# LiBatteryChargeBoostBoard.net
KiCad netlist of a schematic drawn in EAGLE
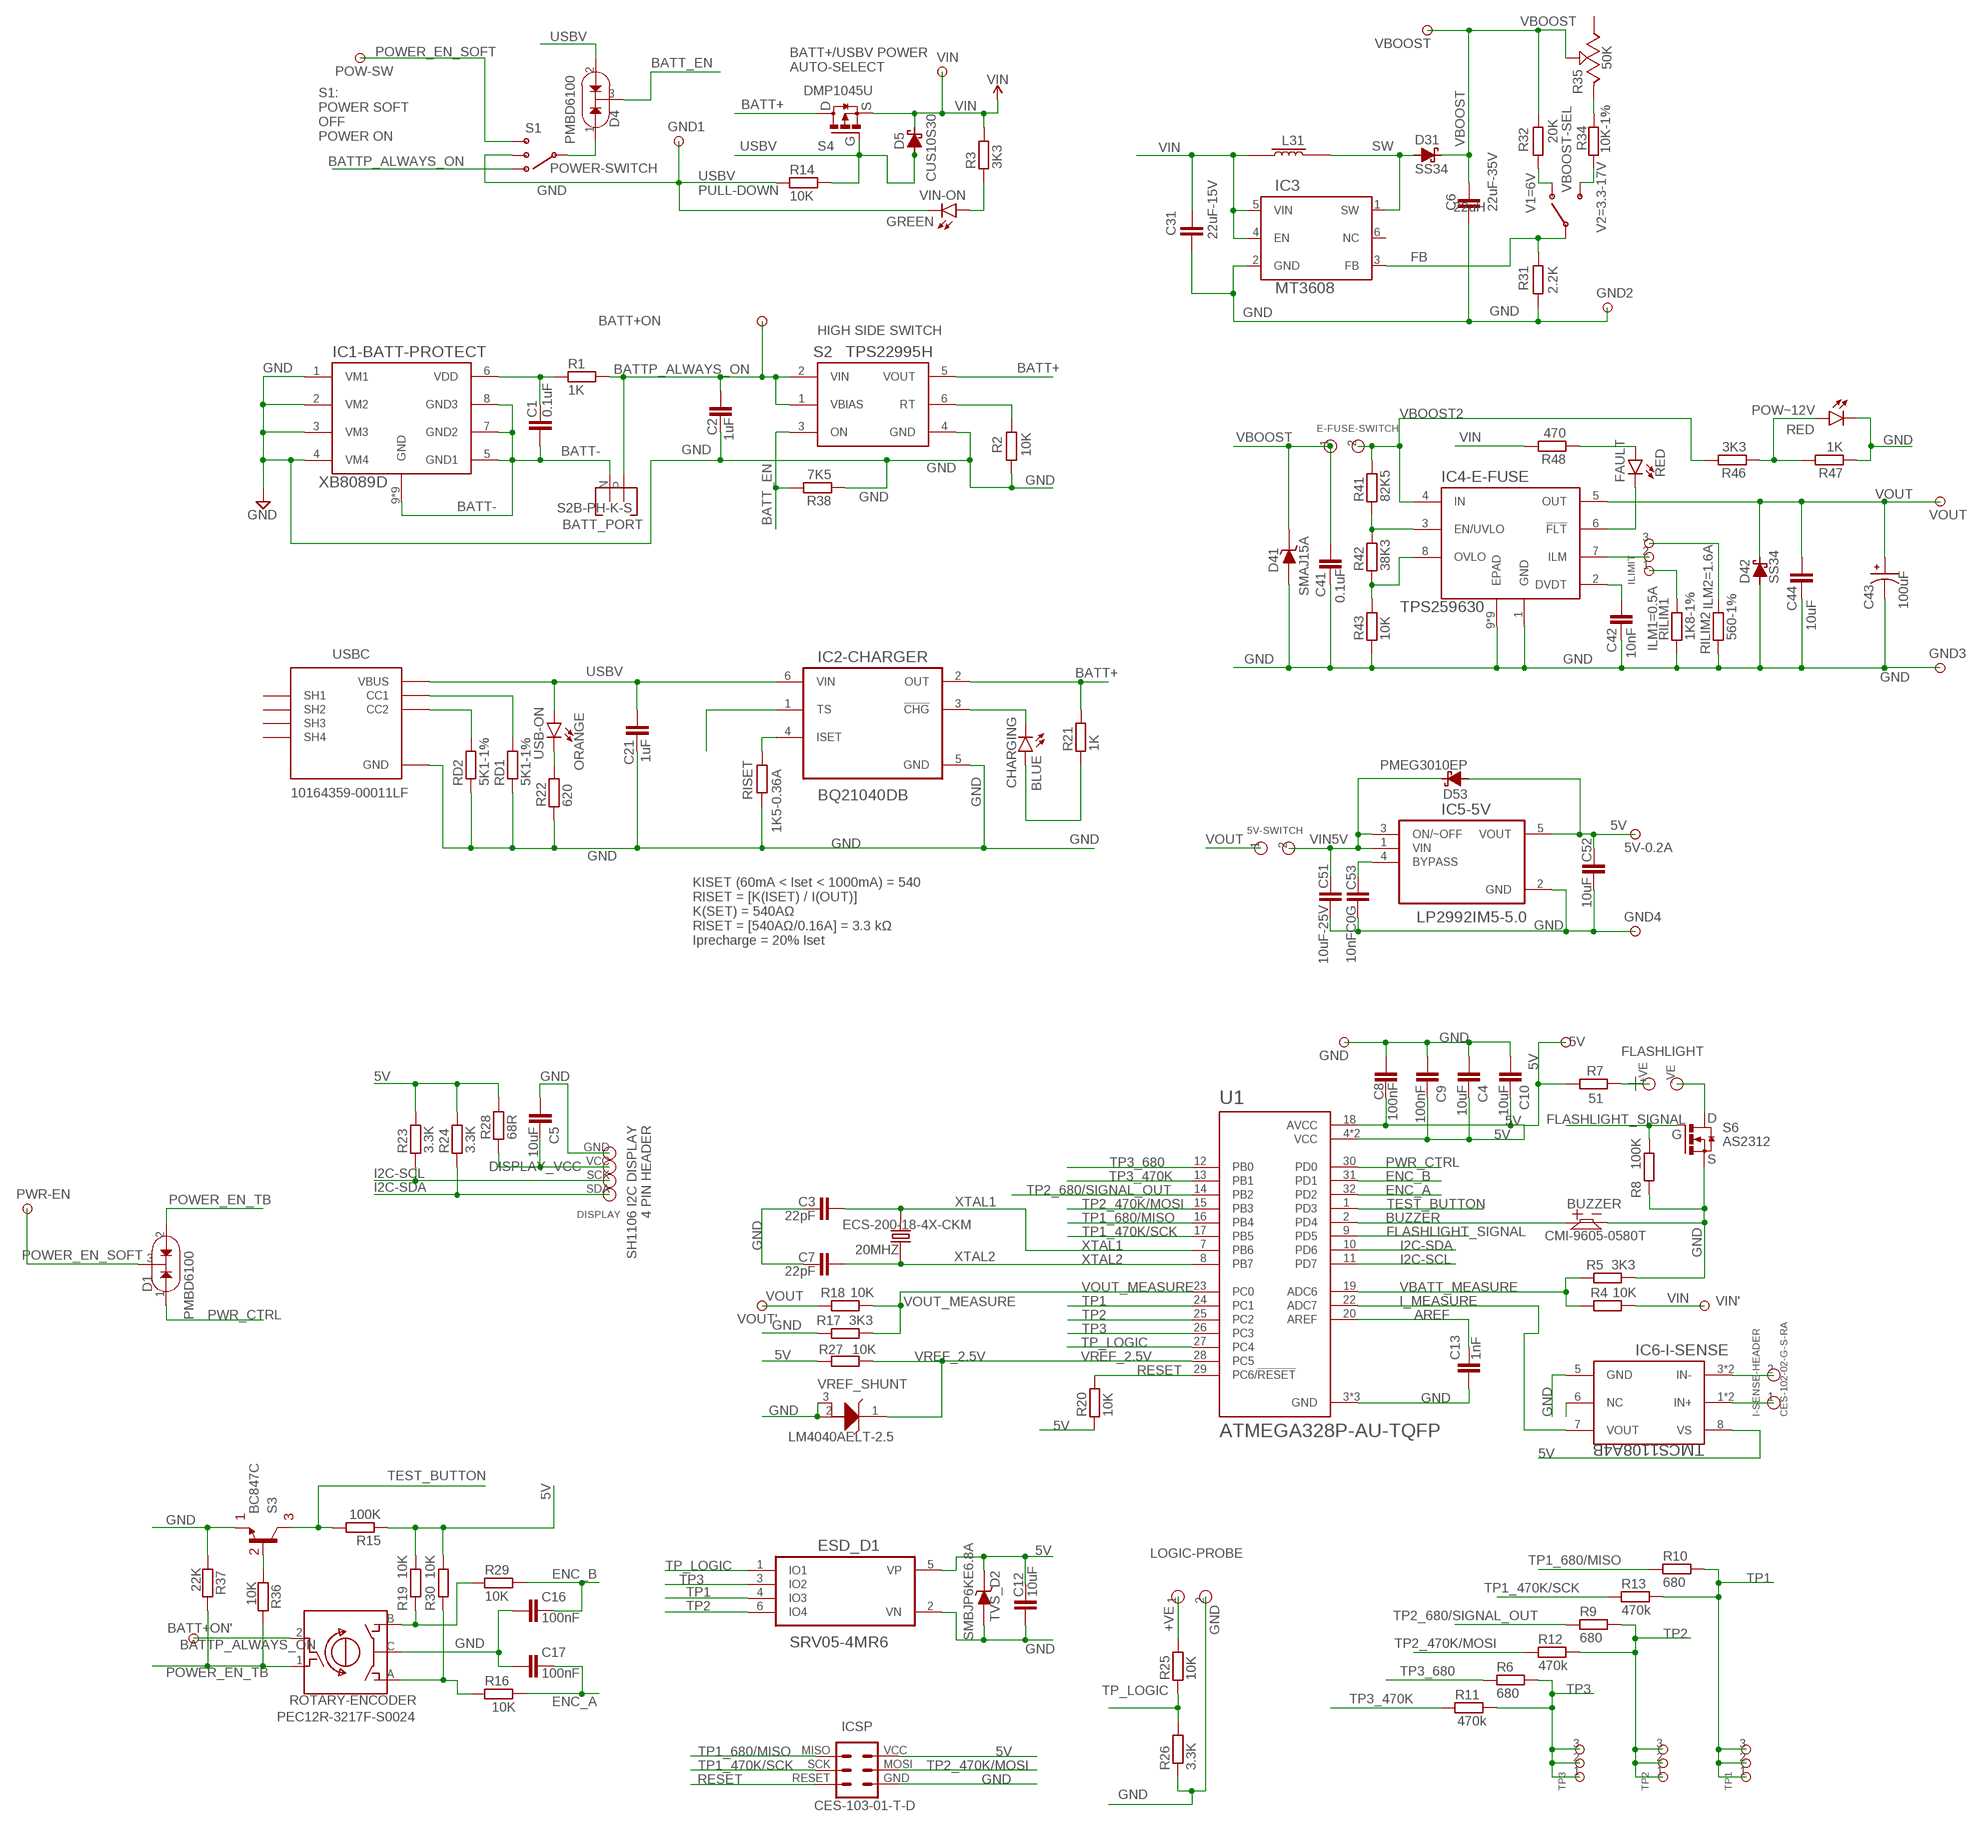
[diagram p0: schematic, sheet 1]

(export (version "E")
  (design (tool "Eeschema 10.0.6"))
  (components
    (comp (ref "5V")
      (value "TEST-POINT-TH")
      (footprint "eagle-import:TEST-POINT-TH-1MM")
      (libsource (lib "eagle-import") (part "TEST-POINT-TH"))
    )
    (comp (ref "5V-0.2A")
      (value "TEST-POINT-TH")
      (footprint "eagle-import:TEST-POINT-TH-1MM")
      (libsource (lib "eagle-import") (part "TEST-POINT-TH"))
    )
    (comp (ref "5V-SWITCH")
      (value "HEADER-2PIN-0.1\"P")
      (footprint "eagle-import:HEADER-2PIN-0.1_P")
      (libsource (lib "eagle-import") (part "HEADER-2PIN-0.1{dblquote}P"))
    )
    (comp (ref "20MHZ")
      (value "ECS-200-18-4X-CKM")
      (footprint "eagle-import:XTAL_ECS-200-18-4X-CKM")
      (fields (field (name "MF") "ECS Inc."))
      (libsource (lib "eagle-import") (part "CRYSTAL-20MHZ-ECS-200-18-4X-CKM"))
    )
    (comp (ref "BATT+ON")
      (value "TEST-POINT-TH")
      (footprint "eagle-import:TEST-POINT-TH-1MM")
      (libsource (lib "eagle-import") (part "TEST-POINT-TH"))
    )
    (comp (ref "BATT+ON'")
      (value "TEST-POINT-TH")
      (footprint "eagle-import:TEST-POINT-TH-1MM")
      (libsource (lib "eagle-import") (part "TEST-POINT-TH"))
    )
    (comp (ref "BATT_PORT")
      (value "S2B-PH-K-S")
      (footprint "eagle-import:S2B-PH-K-S")
      (libsource (lib "eagle-import") (part "S2B-PH-K-S"))
    )
    (comp (ref "BUZZER")
      (value "CMI-9605-0580T")
      (footprint "eagle-import:BUZZER-ACTIVE-CMI-9605-0580T")
      (libsource (lib "eagle-import") (part "BUZZER-ACTIVE-CMI-9605-0580T"))
    )
    (comp (ref "C1")
      (value "0.1uF")
      (footprint "eagle-import:0603")
      (libsource (lib "eagle-import") (part "CAPACITOR_SMD0603"))
    )
    (comp (ref "C2")
      (value "1uF")
      (footprint "eagle-import:0603")
      (libsource (lib "eagle-import") (part "CAPACITOR_SMD0603"))
    )
    (comp (ref "C3")
      (value "22pF")
      (footprint "eagle-import:0603")
      (libsource (lib "eagle-import") (part "CAPACITOR_SMD0603"))
    )
    (comp (ref "C4")
      (value "10uF")
      (footprint "eagle-import:0603")
      (libsource (lib "eagle-import") (part "CAPACITOR_SMD0603"))
    )
    (comp (ref "C5")
      (value "10uF")
      (footprint "eagle-import:0603")
      (libsource (lib "eagle-import") (part "CAPACITOR_SMD0603"))
    )
    (comp (ref "C6")
      (value "22uF-35V")
      (footprint "eagle-import:1206")
      (libsource (lib "eagle-import") (part "CAPACITOR_SMD1206"))
    )
    (comp (ref "C7")
      (value "22pF")
      (footprint "eagle-import:0603")
      (libsource (lib "eagle-import") (part "CAPACITOR_SMD0603"))
    )
    (comp (ref "C8")
      (value "100nF")
      (footprint "eagle-import:0603")
      (libsource (lib "eagle-import") (part "CAPACITOR_SMD0603"))
    )
    (comp (ref "C9")
      (value "100nF")
      (footprint "eagle-import:0603")
      (libsource (lib "eagle-import") (part "CAPACITOR_SMD0603"))
    )
    (comp (ref "C10")
      (value "10uF")
      (footprint "eagle-import:0603")
      (libsource (lib "eagle-import") (part "CAPACITOR_SMD0603"))
    )
    (comp (ref "C12")
      (value "10uF")
      (footprint "eagle-import:0603")
      (libsource (lib "eagle-import") (part "CAPACITOR_SMD0603"))
    )
    (comp (ref "C13")
      (value "1nF")
      (footprint "eagle-import:0603")
      (libsource (lib "eagle-import") (part "CAPACITOR_SMD0603"))
    )
    (comp (ref "C16")
      (value "100nF")
      (footprint "eagle-import:0603")
      (libsource (lib "eagle-import") (part "CAPACITOR_SMD0603"))
    )
    (comp (ref "C17")
      (value "100nF")
      (footprint "eagle-import:0603")
      (libsource (lib "eagle-import") (part "CAPACITOR_SMD0603"))
    )
    (comp (ref "C21")
      (value "1uF")
      (footprint "eagle-import:0603")
      (libsource (lib "eagle-import") (part "CAPACITOR_SMD0603"))
    )
    (comp (ref "C31")
      (value "22uF-15V")
      (footprint "eagle-import:1206")
      (libsource (lib "eagle-import") (part "CAPACITOR_SMD1206"))
    )
    (comp (ref "C41")
      (value "0.1uF")
      (footprint "eagle-import:0603")
      (libsource (lib "eagle-import") (part "CAPACITOR_SMD0603"))
    )
    (comp (ref "C42")
      (value "10nF")
      (footprint "eagle-import:0603")
      (libsource (lib "eagle-import") (part "CAPACITOR_SMD0603"))
    )
    (comp (ref "C43")
      (value "100uF")
      (footprint "eagle-import:CAP_EEEFN1E101UP")
      (fields (field (name "MF") "Panasonic Electronic Components") (field (name "MP") "EEE-FN1E101UP"))
      (libsource (lib "eagle-import") (part "EEEFN1E101UP"))
    )
    (comp (ref "C44")
      (value "10uF")
      (footprint "eagle-import:0603")
      (libsource (lib "eagle-import") (part "CAPACITOR_SMD0603"))
    )
    (comp (ref "C51")
      (value "10uF-25V")
      (footprint "eagle-import:0603")
      (libsource (lib "eagle-import") (part "CAPACITOR0603"))
    )
    (comp (ref "C52")
      (value "10uF")
      (footprint "eagle-import:0603")
      (libsource (lib "eagle-import") (part "CAPACITOR0603"))
    )
    (comp (ref "C53")
      (value "10nFC0G")
      (footprint "eagle-import:0603")
      (libsource (lib "eagle-import") (part "CAPACITOR_SMD0603"))
    )
    (comp (ref "CHARGING")
      (value "BLUE")
      (footprint "eagle-import:0603-DIODE")
      (libsource (lib "eagle-import") (part "LED0603"))
    )
    (comp (ref "D1")
      (value "PMBD6100")
      (footprint "eagle-import:SOT-23-3")
      (libsource (lib "eagle-import") (part "DIODE-DOUBLE-COMMON-CATHODE-PMBD6100,215"))
    )
    (comp (ref "D4")
      (value "PMBD6100")
      (footprint "eagle-import:SOT-23-3")
      (libsource (lib "eagle-import") (part "DIODE-DOUBLE-COMMON-CATHODE-PMBD6100,215"))
    )
    (comp (ref "D5")
      (value "CUS10S30")
      (footprint "eagle-import:SOD-323")
      (libsource (lib "eagle-import") (part "DIODE-SCHOTTKY-CUS10S30,H3F"))
    )
    (comp (ref "D31")
      (value "SS34")
      (footprint "eagle-import:SMA")
      (libsource (lib "eagle-import") (part "DIODE-SCHOTTKY-SS34"))
    )
    (comp (ref "D41")
      (value "SMAJ15A")
      (footprint "eagle-import:SMA")
      (libsource (lib "eagle-import") (part "DIODE-TVS-SMA"))
    )
    (comp (ref "D42")
      (value "SS34")
      (footprint "eagle-import:SMA")
      (libsource (lib "eagle-import") (part "DIODE-SCHOTTKY-SS34"))
    )
    (comp (ref "D53")
      (value "PMEG3010EP")
      (footprint "eagle-import:SOD-128")
      (libsource (lib "eagle-import") (part "DIODE-SCHOTTKY-PMEG3010EP,115"))
    )
    (comp (ref "DISPLAY")
      (value "DISPLAY-1.3\"-SH1106-I2C")
      (footprint "eagle-import:DISPLAY-1.3_-SH1106-I2C")
      (libsource (lib "eagle-import") (part "DISPLAY-1.3{dblquote}-SH1106-I2C"))
    )
    (comp (ref "E-FUSE-SWITCH")
      (value "HEADER-2PIN-0.1\"P")
      (footprint "eagle-import:HEADER-2PIN-0.1_P")
      (libsource (lib "eagle-import") (part "HEADER-2PIN-0.1{dblquote}P"))
    )
    (comp (ref "ESD_D1")
      (value "SRV05-4MR6")
      (footprint "eagle-import:SOT-23-6")
      (fields (field (name "MF") "ON Semiconductor") (field (name "MP") "SRV05-4MR6T1G"))
      (libsource (lib "eagle-import") (part "SRV05-4MR6T1G"))
    )
    (comp (ref "FAULT")
      (value "RED")
      (footprint "eagle-import:0603-DIODE")
      (libsource (lib "eagle-import") (part "LED0603"))
    )
    (comp (ref "FLASHLIGHT")
      (value "HEADER-2PIN-0.2\"P")
      (footprint "eagle-import:HEADER-2PIN-0.2_P")
      (libsource (lib "eagle-import") (part "HEADER-2PIN-0.2{dblquote}P"))
    )
    (comp (ref "GND")
      (value "TEST-POINT-TH")
      (footprint "eagle-import:TEST-POINT-TH-1MM")
      (libsource (lib "eagle-import") (part "TEST-POINT-TH"))
    )
    (comp (ref "GND1")
      (value "TEST-POINT-TH")
      (footprint "eagle-import:TEST-POINT-TH-1MM")
      (libsource (lib "eagle-import") (part "TEST-POINT-TH"))
    )
    (comp (ref "GND2")
      (value "TEST-POINT-TH")
      (footprint "eagle-import:TEST-POINT-TH-1MM")
      (libsource (lib "eagle-import") (part "TEST-POINT-TH"))
    )
    (comp (ref "GND3")
      (value "TEST-POINT-TH")
      (footprint "eagle-import:TEST-POINT-TH-1MM")
      (libsource (lib "eagle-import") (part "TEST-POINT-TH"))
    )
    (comp (ref "GND4")
      (value "TEST-POINT-TH")
      (footprint "eagle-import:TEST-POINT-TH-1MM")
      (libsource (lib "eagle-import") (part "TEST-POINT-TH"))
    )
    (comp (ref "I-SENSE-HEADER")
      (value "CES-102-02-G-S-RA")
      (footprint "eagle-import:HEADER-2PIN-0.1_P")
      (libsource (lib "eagle-import") (part "HEADER-2PIN-0.1{dblquote}P"))
    )
    (comp (ref "IC1-BATT-PROTECT")
      (value "XB8089D")
      (footprint "eagle-import:SOIC-8-POWER-PAD")
      (libsource (lib "eagle-import") (part "XB8089D"))
    )
    (comp (ref "IC2-CHARGER")
      (value "BQ21040DB")
      (footprint "eagle-import:SOT-23-6")
      (fields (field (name "MF") "Texas Instruments") (field (name "MP") "BQ21040DBVR"))
      (libsource (lib "eagle-import") (part "BQ21040DBVR"))
    )
    (comp (ref "IC3")
      (value "MT3608")
      (footprint "eagle-import:SOT-23-6")
      (libsource (lib "eagle-import") (part "MT3608"))
    )
    (comp (ref "IC4-E-FUSE")
      (value "TPS259630")
      (footprint "eagle-import:SOIC-8-POWER-PAD")
      (libsource (lib "eagle-import") (part "TPS259621DDAR"))
    )
    (comp (ref "IC5-5V")
      (value "LP2992IM5-5.0")
      (footprint "eagle-import:SOT-23-5")
      (fields (field (name "MF") "Texas Instruments") (field (name "MP") "LP2992IM5-5.0/NOPB"))
      (libsource (lib "eagle-import") (part "LP2992IM5-5.0"))
    )
    (comp (ref "IC6-I-SENSE")
      (value "TMCS1108A4B")
      (footprint "eagle-import:SOIC-8")
      (libsource (lib "eagle-import") (part "TMCS1108A4B-CURRENT-SENSE"))
    )
    (comp (ref "ICSP")
      (value "CES-103-01-T-D")
      (footprint "eagle-import:HEADER-ICSP-0.1_P")
      (libsource (lib "eagle-import") (part "HEADER-ICSP-0.1{dblquote}P"))
    )
    (comp (ref "ILIMIT")
      (value "HEADER-3PIN-0.1\"P")
      (footprint "eagle-import:HEADER-3PIN-0.1_P")
      (libsource (lib "eagle-import") (part "HEADER-3PIN-0.1{dblquote}P"))
    )
    (comp (ref "L31")
      (value "22uH")
      (footprint "eagle-import:INDUCTOR-SMRH74-220MT")
      (libsource (lib "eagle-import") (part "INDUCTOR-SMRH74-220MT"))
    )
    (comp (ref "LOGIC-PROBE")
      (value "HEADER-2PIN-0.1\"P")
      (footprint "eagle-import:HEADER-2PIN-0.1_P")
      (libsource (lib "eagle-import") (part "HEADER-2PIN-0.1{dblquote}P"))
    )
    (comp (ref "POW-SW")
      (value "TEST-POINT-TH")
      (footprint "eagle-import:TEST-POINT-TH-1MM")
      (libsource (lib "eagle-import") (part "TEST-POINT-TH"))
    )
    (comp (ref "POW~12V")
      (value "RED")
      (footprint "eagle-import:1206-DIODE")
      (libsource (lib "eagle-import") (part "LED1206"))
    )
    (comp (ref "PWR-EN")
      (value "TEST-POINT-TH")
      (footprint "eagle-import:TEST-POINT-TH-1MM")
      (libsource (lib "eagle-import") (part "TEST-POINT-TH"))
    )
    (comp (ref "R1")
      (value "1K")
      (footprint "eagle-import:0603")
      (libsource (lib "eagle-import") (part "RESISTOR_SMD0603"))
    )
    (comp (ref "R2")
      (value "10K")
      (footprint "eagle-import:0603")
      (libsource (lib "eagle-import") (part "RESISTOR_SMD0603"))
    )
    (comp (ref "R3")
      (value "3K3")
      (footprint "eagle-import:0603")
      (libsource (lib "eagle-import") (part "RESISTOR_SMD0603"))
    )
    (comp (ref "R4")
      (value "10K")
      (footprint "eagle-import:0603")
      (libsource (lib "eagle-import") (part "RESISTOR_SMD0603"))
    )
    (comp (ref "R5")
      (value "3K3")
      (footprint "eagle-import:0603")
      (libsource (lib "eagle-import") (part "RESISTOR_SMD0603"))
    )
    (comp (ref "R6")
      (value "680")
      (footprint "eagle-import:1206")
      (libsource (lib "eagle-import") (part "RESISTOR_SMD1206"))
    )
    (comp (ref "R7")
      (value "51")
      (footprint "eagle-import:1206")
      (libsource (lib "eagle-import") (part "RESISTOR_SMD1206"))
    )
    (comp (ref "R8")
      (value "100K")
      (footprint "eagle-import:0603")
      (libsource (lib "eagle-import") (part "RESISTOR_SMD0603"))
    )
    (comp (ref "R9")
      (value "680")
      (footprint "eagle-import:1206")
      (libsource (lib "eagle-import") (part "RESISTOR_SMD1206"))
    )
    (comp (ref "R10")
      (value "680")
      (footprint "eagle-import:1206")
      (libsource (lib "eagle-import") (part "RESISTOR_SMD1206"))
    )
    (comp (ref "R11")
      (value "470k")
      (footprint "eagle-import:1206")
      (libsource (lib "eagle-import") (part "RESISTOR_SMD1206"))
    )
    (comp (ref "R12")
      (value "470k")
      (footprint "eagle-import:1206")
      (libsource (lib "eagle-import") (part "RESISTOR_SMD1206"))
    )
    (comp (ref "R13")
      (value "470k")
      (footprint "eagle-import:1206")
      (libsource (lib "eagle-import") (part "RESISTOR_SMD1206"))
    )
    (comp (ref "R14")
      (value "10K")
      (footprint "eagle-import:0603")
      (libsource (lib "eagle-import") (part "RESISTOR_SMD0603"))
    )
    (comp (ref "R15")
      (value "100K")
      (footprint "eagle-import:0603")
      (libsource (lib "eagle-import") (part "RESISTOR_SMD0603"))
    )
    (comp (ref "R16")
      (value "10K")
      (footprint "eagle-import:0603")
      (libsource (lib "eagle-import") (part "RESISTOR_SMD0603"))
    )
    (comp (ref "R17")
      (value "3K3")
      (footprint "eagle-import:0603")
      (libsource (lib "eagle-import") (part "RESISTOR_SMD0603"))
    )
    (comp (ref "R18")
      (value "10K")
      (footprint "eagle-import:0603")
      (libsource (lib "eagle-import") (part "RESISTOR_SMD0603"))
    )
    (comp (ref "R19")
      (value "10K")
      (footprint "eagle-import:0603")
      (libsource (lib "eagle-import") (part "RESISTOR_SMD0603"))
    )
    (comp (ref "R20")
      (value "10K")
      (footprint "eagle-import:0603")
      (libsource (lib "eagle-import") (part "RESISTOR_SMD0603"))
    )
    (comp (ref "R21")
      (value "1K")
      (footprint "eagle-import:0603")
      (libsource (lib "eagle-import") (part "RESISTOR_SMD0603"))
    )
    (comp (ref "R22")
      (value "620")
      (footprint "eagle-import:0603")
      (libsource (lib "eagle-import") (part "RESISTOR_SMD0603"))
    )
    (comp (ref "R23")
      (value "3.3K")
      (footprint "eagle-import:0603")
      (libsource (lib "eagle-import") (part "RESISTOR_SMD0603"))
    )
    (comp (ref "R24")
      (value "3.3K")
      (footprint "eagle-import:0603")
      (libsource (lib "eagle-import") (part "RESISTOR_SMD0603"))
    )
    (comp (ref "R25")
      (value "10K")
      (footprint "eagle-import:0603")
      (libsource (lib "eagle-import") (part "RESISTOR_SMD0603"))
    )
    (comp (ref "R26")
      (value "3.3K")
      (footprint "eagle-import:0603")
      (libsource (lib "eagle-import") (part "RESISTOR_SMD0603"))
    )
    (comp (ref "R27")
      (value "10K")
      (footprint "eagle-import:0603")
      (libsource (lib "eagle-import") (part "RESISTOR_SMD0603"))
    )
    (comp (ref "R28")
      (value "68R")
      (footprint "eagle-import:0603")
      (libsource (lib "eagle-import") (part "RESISTOR_SMD0603"))
    )
    (comp (ref "R29")
      (value "10K")
      (footprint "eagle-import:0603")
      (libsource (lib "eagle-import") (part "RESISTOR_SMD0603"))
    )
    (comp (ref "R30")
      (value "10K")
      (footprint "eagle-import:0603")
      (libsource (lib "eagle-import") (part "RESISTOR_SMD0603"))
    )
    (comp (ref "R31")
      (value "2.2K")
      (footprint "eagle-import:0603")
      (libsource (lib "eagle-import") (part "RESISTOR_SMD0603"))
    )
    (comp (ref "R32")
      (value "20K")
      (footprint "eagle-import:0603")
      (libsource (lib "eagle-import") (part "RESISTOR_SMD0603"))
    )
    (comp (ref "R34")
      (value "10K-1%")
      (footprint "eagle-import:0603")
      (libsource (lib "eagle-import") (part "RESISTOR_SMD0603"))
    )
    (comp (ref "R35")
      (value "50K")
      (footprint "eagle-import:ROTARY-POTENTIOMETER-3386P")
      (libsource (lib "eagle-import") (part "ROTARY-POTENTIOMETER-3386P-1-503TLF"))
    )
    (comp (ref "R36")
      (value "10K")
      (footprint "eagle-import:0603")
      (libsource (lib "eagle-import") (part "RESISTOR_SMD0603"))
    )
    (comp (ref "R37")
      (value "22K")
      (footprint "eagle-import:0603")
      (libsource (lib "eagle-import") (part "RESISTOR_SMD0603"))
    )
    (comp (ref "R38")
      (value "7K5")
      (footprint "eagle-import:0603")
      (libsource (lib "eagle-import") (part "RESISTOR_SMD0603"))
    )
    (comp (ref "R41")
      (value "82K5")
      (footprint "eagle-import:0603")
      (libsource (lib "eagle-import") (part "RESISTOR_SMD0603"))
    )
    (comp (ref "R42")
      (value "38K3")
      (footprint "eagle-import:0603")
      (libsource (lib "eagle-import") (part "RESISTOR_SMD0603"))
    )
    (comp (ref "R43")
      (value "10K")
      (footprint "eagle-import:0603")
      (libsource (lib "eagle-import") (part "RESISTOR_SMD0603"))
    )
    (comp (ref "R46")
      (value "3K3")
      (footprint "eagle-import:0603")
      (libsource (lib "eagle-import") (part "RESISTOR_SMD0603"))
    )
    (comp (ref "R47")
      (value "1K")
      (footprint "eagle-import:0603")
      (libsource (lib "eagle-import") (part "RESISTOR_SMD0603"))
    )
    (comp (ref "R48")
      (value "470")
      (footprint "eagle-import:0603")
      (libsource (lib "eagle-import") (part "RESISTOR_SMD0603"))
    )
    (comp (ref "RD1")
      (value "5K1-1%")
      (footprint "eagle-import:0603")
      (libsource (lib "eagle-import") (part "RESISTOR_SMD0603"))
    )
    (comp (ref "RD2")
      (value "5K1-1%")
      (footprint "eagle-import:0603")
      (libsource (lib "eagle-import") (part "RESISTOR_SMD0603"))
    )
    (comp (ref "RILIM1")
      (value "1K8-1%")
      (footprint "eagle-import:0603")
      (libsource (lib "eagle-import") (part "RESISTOR_SMD0603"))
    )
    (comp (ref "RILIM2")
      (value "560-1%")
      (footprint "eagle-import:0603")
      (libsource (lib "eagle-import") (part "RESISTOR_SMD0603"))
    )
    (comp (ref "RISET")
      (value "1K5-0.36A")
      (footprint "eagle-import:0603")
      (libsource (lib "eagle-import") (part "RESISTOR_SMD0603"))
    )
    (comp (ref "ROTARY-ENCODER")
      (value "PEC12R-3217F-S0024")
      (footprint "eagle-import:PEC12R-3217F-S0024")
      (libsource (lib "eagle-import") (part "PEC12R-3217F-S0024"))
    )
    (comp (ref "S1")
      (value "POWER-SWITCH")
      (footprint "eagle-import:CSS-1310MC")
      (libsource (lib "eagle-import") (part "SLIDE-SWITCH-SP3T-VER-TH-MINI"))
    )
    (comp (ref "S2")
      (value "TPS22995H")
      (footprint "eagle-import:SOT-23-6")
      (libsource (lib "eagle-import") (part "TPS22995H-Q1"))
    )
    (comp (ref "S3")
      (value "BC847C")
      (footprint "eagle-import:SOT-23-3")
      (libsource (lib "eagle-import") (part "BC847C"))
    )
    (comp (ref "S4")
      (value "DMP1045U")
      (footprint "eagle-import:SOT-23-3")
      (libsource (lib "eagle-import") (part "DMP1045U"))
    )
    (comp (ref "S6")
      (value "AS2312")
      (footprint "eagle-import:SOT-23-3")
      (libsource (lib "eagle-import") (part "AS2312AS2312"))
    )
    (comp (ref "TP1")
      (value "HEADER-3PIN-0.1\"P")
      (footprint "eagle-import:HEADER-3PIN-0.1_P")
      (libsource (lib "eagle-import") (part "HEADER-3PIN-0.1{dblquote}P"))
    )
    (comp (ref "TP2")
      (value "HEADER-3PIN-0.1\"P")
      (footprint "eagle-import:HEADER-3PIN-0.1_P")
      (libsource (lib "eagle-import") (part "HEADER-3PIN-0.1{dblquote}P"))
    )
    (comp (ref "TP3")
      (value "HEADER-3PIN-0.1\"P")
      (footprint "eagle-import:HEADER-3PIN-0.1_P")
      (libsource (lib "eagle-import") (part "HEADER-3PIN-0.1{dblquote}P"))
    )
    (comp (ref "TVS_D2")
      (value "SMBJP6KE6.8A")
      (footprint "eagle-import:DIOM5336X244N")
      (fields
        (field (name "DIGIKEY_PART_NUMBER") "SMBJP6KE6.8A-TPMSTR-ND")
        (field (name "MF") "Micro Commercial")
        (field (name "MP") "SMBJP6KE6.8A-TP")
      )
      (libsource (lib "eagle-import") (part "SMBJP6KE6.8A-TP"))
    )
    (comp (ref "U1")
      (value "ATMEGA328P-AU-TQFP")
      (footprint "eagle-import:TQFP32")
      (fields (field (name "MF") "Microchip") (field (name "MP") "ATMEGA328P-AU"))
      (libsource (lib "eagle-import") (part "ATMEGA328P-AU-TQFP"))
    )
    (comp (ref "USB-ON")
      (value "ORANGE")
      (footprint "eagle-import:0603-DIODE")
      (libsource (lib "eagle-import") (part "LED0603"))
    )
    (comp (ref "USBC")
      (value "10164359-00011LF")
      (footprint "eagle-import:USB-C-RECEPTABLE-1016435900011LF")
      (fields (field (name "MF") "Amphenol FCI"))
      (libsource (lib "eagle-import") (part "USB-C-RECEPTABLE-10164359-00011LF"))
    )
    (comp (ref "VBOOST")
      (value "TEST-POINT-TH")
      (footprint "eagle-import:TEST-POINT-TH-1MM")
      (libsource (lib "eagle-import") (part "TEST-POINT-TH"))
    )
    (comp (ref "VBOOST-SEL")
      (value "SLIDE-SWITCH-SPDT-VERTICLE-TH")
      (footprint "eagle-import:SLW-883935-2A-D")
      (libsource (lib "eagle-import") (part "SLIDE-SWITCH-SPDT-VERTICLE-TH"))
    )
    (comp (ref "VIN")
      (value "TEST-POINT-TH")
      (footprint "eagle-import:TEST-POINT-TH-1MM")
      (libsource (lib "eagle-import") (part "TEST-POINT-TH"))
    )
    (comp (ref "VIN'")
      (value "TEST-POINT-TH")
      (footprint "eagle-import:TEST-POINT-TH-1MM")
      (libsource (lib "eagle-import") (part "TEST-POINT-TH"))
    )
    (comp (ref "VIN-ON")
      (value "GREEN")
      (footprint "eagle-import:0603-DIODE")
      (libsource (lib "eagle-import") (part "LED0603"))
    )
    (comp (ref "VOUT")
      (value "TEST-POINT-TH")
      (footprint "eagle-import:TEST-POINT-TH-1MM")
      (libsource (lib "eagle-import") (part "TEST-POINT-TH"))
    )
    (comp (ref "VOUT'")
      (value "TEST-POINT-TH")
      (footprint "eagle-import:TEST-POINT-TH-1MM")
      (libsource (lib "eagle-import") (part "TEST-POINT-TH"))
    )
    (comp (ref "VREF_SHUNT")
      (value "LM4040AELT-2.5")
      (footprint "eagle-import:SOT-23-3")
      (libsource (lib "eagle-import") (part "LM4040AELT-2.5-SOT23"))
    )
  )
  (nets
    (net (code "1") (name "/+VE") (class "Default")
      (node (ref "LOGIC-PROBE") (pin "1") (pinfunction "P$1_1") (pintype "bidirectional"))
      (node (ref "R25") (pin "2") (pinfunction "2_2") (pintype "passive"))
    )
    (net (code "2") (name "/5V") (class "Default")
      (node (ref "5V") (pin "P$1") (pinfunction "P$1_P$1") (pintype "bidirectional"))
      (node (ref "5V-0.2A") (pin "P$1") (pinfunction "P$1_P$1") (pintype "bidirectional"))
      (node (ref "C10") (pin "1") (pinfunction "1_1") (pintype "passive"))
      (node (ref "C12") (pin "1") (pinfunction "1_1") (pintype "passive"))
      (node (ref "C4") (pin "1") (pinfunction "1_1") (pintype "passive"))
      (node (ref "C52") (pin "2") (pinfunction "2_2") (pintype "passive"))
      (node (ref "C8") (pin "2") (pinfunction "2_2") (pintype "passive"))
      (node (ref "C9") (pin "1") (pinfunction "1_1") (pintype "passive"))
      (node (ref "D53") (pin "A") (pinfunction "A_A") (pintype "passive"))
      (node (ref "ESD_D1") (pin "5") (pinfunction "VP_5") (pintype "power_in"))
      (node (ref "IC5-5V") (pin "5") (pinfunction "VOUT_5") (pintype "output"))
      (node (ref "IC6-I-SENSE") (pin "8") (pinfunction "VS_8") (pintype "input"))
      (node (ref "ICSP") (pin "VCC") (pinfunction "2_VCC") (pintype "passive"))
      (node (ref "R15") (pin "1") (pinfunction "1_1") (pintype "passive"))
      (node (ref "R19") (pin "2") (pinfunction "2_2") (pintype "passive"))
      (node (ref "R20") (pin "1") (pinfunction "1_1") (pintype "passive"))
      (node (ref "R23") (pin "2") (pinfunction "2_2") (pintype "passive"))
      (node (ref "R24") (pin "2") (pinfunction "2_2") (pintype "passive"))
      (node (ref "R27") (pin "1") (pinfunction "1_1") (pintype "passive"))
      (node (ref "R28") (pin "2") (pinfunction "2_2") (pintype "passive"))
      (node (ref "R30") (pin "2") (pinfunction "2_2") (pintype "passive"))
      (node (ref "R7") (pin "1") (pinfunction "1_1") (pintype "passive"))
      (node (ref "TVS_D2") (pin "C") (pinfunction "C_C") (pintype "passive"))
      (node (ref "U1") (pin "18") (pinfunction "AVCC_18") (pintype "power_in"))
      (node (ref "U1") (pin "4") (pinfunction "VCC_4") (pintype "power_in"))
      (node (ref "U1") (pin "6") (pinfunction "VCC_6") (pintype "power_in"))
    )
    (net (code "3") (name "/AREF") (class "Default")
      (node (ref "C13") (pin "1") (pinfunction "1_1") (pintype "passive"))
      (node (ref "U1") (pin "20") (pinfunction "AREF_20") (pintype "input"))
    )
    (net (code "4") (name "/BATT+") (class "Default")
      (node (ref "IC2-CHARGER") (pin "2") (pinfunction "OUT_2") (pintype "output"))
      (node (ref "R21") (pin "2") (pinfunction "2_2") (pintype "passive"))
      (node (ref "S2") (pin "5") (pinfunction "VOUT_5") (pintype "output"))
      (node (ref "S4") (pin "3") (pinfunction "D_3") (pintype "passive"))
    )
    (net (code "5") (name "/BATT-") (class "Default")
      (node (ref "BATT_PORT") (pin "N") (pinfunction "N_N") (pintype "bidirectional"))
      (node (ref "C1") (pin "2") (pinfunction "2_2") (pintype "passive"))
      (node (ref "IC1-BATT-PROTECT") (pin "10") (pinfunction "GND_10") (pintype "power_in"))
      (node (ref "IC1-BATT-PROTECT") (pin "11") (pinfunction "GND_11") (pintype "power_in"))
      (node (ref "IC1-BATT-PROTECT") (pin "12") (pinfunction "GND_12") (pintype "power_in"))
      (node (ref "IC1-BATT-PROTECT") (pin "13") (pinfunction "GND_13") (pintype "power_in"))
      (node (ref "IC1-BATT-PROTECT") (pin "14") (pinfunction "GND_14") (pintype "power_in"))
      (node (ref "IC1-BATT-PROTECT") (pin "15") (pinfunction "GND_15") (pintype "power_in"))
      (node (ref "IC1-BATT-PROTECT") (pin "16") (pinfunction "GND_16") (pintype "power_in"))
      (node (ref "IC1-BATT-PROTECT") (pin "17") (pinfunction "GND_17") (pintype "power_in"))
      (node (ref "IC1-BATT-PROTECT") (pin "5") (pinfunction "GND1_5") (pintype "power_in"))
      (node (ref "IC1-BATT-PROTECT") (pin "7") (pinfunction "GND2_7") (pintype "power_in"))
      (node (ref "IC1-BATT-PROTECT") (pin "8") (pinfunction "GND3_8") (pintype "power_in"))
      (node (ref "IC1-BATT-PROTECT") (pin "9") (pinfunction "GND_9") (pintype "power_in"))
    )
    (net (code "6") (name "/BATTP_ALWAYS_ON") (class "Default")
      (node (ref "BATT+ON") (pin "P$1") (pinfunction "P$1_P$1") (pintype "bidirectional"))
      (node (ref "BATT+ON'") (pin "P$1") (pinfunction "P$1_P$1") (pintype "bidirectional"))
      (node (ref "BATT_PORT") (pin "P") (pinfunction "P_P") (pintype "bidirectional"))
      (node (ref "C2") (pin "2") (pinfunction "2_2") (pintype "passive"))
      (node (ref "R1") (pin "2") (pinfunction "2_2") (pintype "passive"))
      (node (ref "ROTARY-ENCODER") (pin "2") (pinfunction "2_2") (pintype "bidirectional"))
      (node (ref "S1") (pin "1") (pinfunction "1_1") (pintype "bidirectional"))
      (node (ref "S2") (pin "1") (pinfunction "VBIAS_1") (pintype "output"))
      (node (ref "S2") (pin "2") (pinfunction "VIN_2") (pintype "input"))
    )
    (net (code "7") (name "/BATT_EN") (class "Default")
      (node (ref "D4") (pin "3") (pinfunction "C_3") (pintype "bidirectional"))
      (node (ref "R38") (pin "2") (pinfunction "2_2") (pintype "passive"))
      (node (ref "S2") (pin "3") (pinfunction "ON_3") (pintype "input"))
    )
    (net (code "8") (name "/BUZZER") (class "Default")
      (node (ref "BUZZER") (pin "P$1") (pinfunction "P$1_P$1") (pintype "bidirectional"))
      (node (ref "U1") (pin "2") (pinfunction "PD4_2") (pintype "bidirectional"))
    )
    (net (code "9") (name "/DISPLAY_VCC") (class "Default")
      (node (ref "C5") (pin "1") (pinfunction "1_1") (pintype "passive"))
      (node (ref "DISPLAY") (pin "VCC") (pinfunction "VCC_VCC") (pintype "bidirectional"))
      (node (ref "R28") (pin "1") (pinfunction "1_1") (pintype "passive"))
    )
    (net (code "10") (name "/ENC_A") (class "Default")
      (node (ref "C17") (pin "1") (pinfunction "1_1") (pintype "passive"))
      (node (ref "R16") (pin "2") (pinfunction "2_2") (pintype "passive"))
      (node (ref "U1") (pin "32") (pinfunction "PD2_32") (pintype "bidirectional"))
    )
    (net (code "11") (name "/ENC_B") (class "Default")
      (node (ref "C16") (pin "1") (pinfunction "1_1") (pintype "passive"))
      (node (ref "R29") (pin "2") (pinfunction "2_2") (pintype "passive"))
      (node (ref "U1") (pin "31") (pinfunction "PD1_31") (pintype "bidirectional"))
    )
    (net (code "12") (name "/FB") (class "Default")
      (node (ref "IC3") (pin "3") (pinfunction "FB_3") (pintype "power_in"))
      (node (ref "R31") (pin "1") (pinfunction "1_1") (pintype "passive"))
      (node (ref "VBOOST-SEL") (pin "C") (pinfunction "C_C") (pintype "bidirectional"))
    )
    (net (code "13") (name "/FLASHLIGHT_SIGNAL") (class "Default")
      (node (ref "R8") (pin "1") (pinfunction "1_1") (pintype "passive"))
      (node (ref "S6") (pin "1") (pinfunction "G_1") (pintype "passive"))
      (node (ref "U1") (pin "9") (pinfunction "PD5_9") (pintype "bidirectional"))
    )
    (net (code "14") (name "/I2C-SCL") (class "Default")
      (node (ref "DISPLAY") (pin "SCK") (pinfunction "SCK_SCK") (pintype "bidirectional"))
      (node (ref "R23") (pin "1") (pinfunction "1_1") (pintype "passive"))
      (node (ref "U1") (pin "11") (pinfunction "PD7_11") (pintype "bidirectional"))
    )
    (net (code "15") (name "/I2C-SDA") (class "Default")
      (node (ref "DISPLAY") (pin "SDA") (pinfunction "SDA_SDA") (pintype "bidirectional"))
      (node (ref "R24") (pin "1") (pinfunction "1_1") (pintype "passive"))
      (node (ref "U1") (pin "10") (pinfunction "PD6_10") (pintype "bidirectional"))
    )
    (net (code "16") (name "/I_MEASURE") (class "Default")
      (node (ref "IC6-I-SENSE") (pin "7") (pinfunction "VOUT_7") (pintype "output"))
      (node (ref "U1") (pin "22") (pinfunction "ADC7_22") (pintype "bidirectional"))
    )
    (net (code "17") (name "/POWER_EN_SOFT") (class "Default")
      (node (ref "D1") (pin "3") (pinfunction "C_3") (pintype "bidirectional"))
      (node (ref "POW-SW") (pin "P$1") (pinfunction "P$1_P$1") (pintype "bidirectional"))
      (node (ref "PWR-EN") (pin "P$1") (pinfunction "P$1_P$1") (pintype "bidirectional"))
      (node (ref "S1") (pin "3") (pinfunction "3_3") (pintype "bidirectional"))
    )
    (net (code "18") (name "/POWER_EN_TB") (class "Default")
      (node (ref "D1") (pin "2") (pinfunction "A2_2") (pintype "bidirectional"))
      (node (ref "R36") (pin "2") (pinfunction "2_2") (pintype "passive"))
      (node (ref "R37") (pin "2") (pinfunction "2_2") (pintype "passive"))
      (node (ref "ROTARY-ENCODER") (pin "1") (pinfunction "1_1") (pintype "bidirectional"))
    )
    (net (code "19") (name "/PWR_CTRL") (class "Default")
      (node (ref "D1") (pin "1") (pinfunction "A1_1") (pintype "bidirectional"))
      (node (ref "U1") (pin "30") (pinfunction "PD0_30") (pintype "bidirectional"))
    )
    (net (code "20") (name "/RESET") (class "Default")
      (node (ref "ICSP") (pin "RESET") (pinfunction "5_RESET") (pintype "passive"))
      (node (ref "R20") (pin "2") (pinfunction "2_2") (pintype "passive"))
      (node (ref "U1") (pin "29") (pinfunction "PC6/~{RESET}_29") (pintype "bidirectional"))
    )
    (net (code "21") (name "/SW") (class "Default")
      (node (ref "D31") (pin "A") (pinfunction "A_A") (pintype "passive"))
      (node (ref "IC3") (pin "1") (pinfunction "SW_1") (pintype "output"))
      (node (ref "L31") (pin "P$2") (pinfunction "P$2_P$2") (pintype "bidirectional"))
    )
    (net (code "22") (name "/TEST_BUTTON") (class "Default")
      (node (ref "R15") (pin "2") (pinfunction "2_2") (pintype "passive"))
      (node (ref "S3") (pin "3") (pinfunction "C_3") (pintype "passive"))
      (node (ref "U1") (pin "1") (pinfunction "PD3_1") (pintype "bidirectional"))
    )
    (net (code "23") (name "/TP1") (class "Default")
      (node (ref "ESD_D1") (pin "4") (pinfunction "IO3_4") (pintype "input"))
      (node (ref "R10") (pin "2") (pinfunction "2_2") (pintype "passive"))
      (node (ref "R13") (pin "2") (pinfunction "2_2") (pintype "passive"))
      (node (ref "TP1") (pin "1") (pinfunction "P$1_1") (pintype "bidirectional"))
      (node (ref "TP1") (pin "2") (pinfunction "P$2_2") (pintype "bidirectional"))
      (node (ref "TP1") (pin "3") (pinfunction "P$3_3") (pintype "bidirectional"))
      (node (ref "U1") (pin "24") (pinfunction "PC1_24") (pintype "bidirectional"))
    )
    (net (code "24") (name "/TP1_470K{slash}SCK") (class "Default")
      (node (ref "ICSP") (pin "SCK") (pinfunction "3_SCK") (pintype "passive"))
      (node (ref "R13") (pin "1") (pinfunction "1_1") (pintype "passive"))
      (node (ref "U1") (pin "17") (pinfunction "PB5_17") (pintype "bidirectional"))
    )
    (net (code "25") (name "/TP1_680{slash}MISO") (class "Default")
      (node (ref "ICSP") (pin "MISO") (pinfunction "1_MISO") (pintype "passive"))
      (node (ref "R10") (pin "1") (pinfunction "1_1") (pintype "passive"))
      (node (ref "U1") (pin "16") (pinfunction "PB4_16") (pintype "bidirectional"))
    )
    (net (code "26") (name "/TP2") (class "Default")
      (node (ref "ESD_D1") (pin "6") (pinfunction "IO4_6") (pintype "input"))
      (node (ref "R12") (pin "2") (pinfunction "2_2") (pintype "passive"))
      (node (ref "R9") (pin "2") (pinfunction "2_2") (pintype "passive"))
      (node (ref "TP2") (pin "1") (pinfunction "P$1_1") (pintype "bidirectional"))
      (node (ref "TP2") (pin "2") (pinfunction "P$2_2") (pintype "bidirectional"))
      (node (ref "TP2") (pin "3") (pinfunction "P$3_3") (pintype "bidirectional"))
      (node (ref "U1") (pin "25") (pinfunction "PC2_25") (pintype "bidirectional"))
    )
    (net (code "27") (name "/TP2_470K{slash}MOSI") (class "Default")
      (node (ref "ICSP") (pin "MOSI") (pinfunction "4_MOSI") (pintype "passive"))
      (node (ref "R12") (pin "1") (pinfunction "1_1") (pintype "passive"))
      (node (ref "U1") (pin "15") (pinfunction "PB3_15") (pintype "bidirectional"))
    )
    (net (code "28") (name "/TP2_680{slash}SIGNAL_OUT") (class "Default")
      (node (ref "R9") (pin "1") (pinfunction "1_1") (pintype "passive"))
      (node (ref "U1") (pin "14") (pinfunction "PB2_14") (pintype "bidirectional"))
    )
    (net (code "29") (name "/TP3") (class "Default")
      (node (ref "ESD_D1") (pin "3") (pinfunction "IO2_3") (pintype "input"))
      (node (ref "R11") (pin "2") (pinfunction "2_2") (pintype "passive"))
      (node (ref "R6") (pin "2") (pinfunction "2_2") (pintype "passive"))
      (node (ref "TP3") (pin "1") (pinfunction "P$1_1") (pintype "bidirectional"))
      (node (ref "TP3") (pin "2") (pinfunction "P$2_2") (pintype "bidirectional"))
      (node (ref "TP3") (pin "3") (pinfunction "P$3_3") (pintype "bidirectional"))
      (node (ref "U1") (pin "26") (pinfunction "PC3_26") (pintype "bidirectional"))
    )
    (net (code "30") (name "/TP3_470K") (class "Default")
      (node (ref "R11") (pin "1") (pinfunction "1_1") (pintype "passive"))
      (node (ref "U1") (pin "13") (pinfunction "PB1_13") (pintype "bidirectional"))
    )
    (net (code "31") (name "/TP3_680") (class "Default")
      (node (ref "R6") (pin "1") (pinfunction "1_1") (pintype "passive"))
      (node (ref "U1") (pin "12") (pinfunction "PB0_12") (pintype "bidirectional"))
    )
    (net (code "32") (name "/TP_LOGIC") (class "Default")
      (node (ref "ESD_D1") (pin "1") (pinfunction "IO1_1") (pintype "input"))
      (node (ref "R25") (pin "1") (pinfunction "1_1") (pintype "passive"))
      (node (ref "R26") (pin "2") (pinfunction "2_2") (pintype "passive"))
      (node (ref "U1") (pin "27") (pinfunction "PC4_27") (pintype "bidirectional"))
    )
    (net (code "33") (name "/USBV") (class "Default")
      (node (ref "C21") (pin "2") (pinfunction "2_2") (pintype "passive"))
      (node (ref "D4") (pin "2") (pinfunction "A2_2") (pintype "bidirectional"))
      (node (ref "D5") (pin "A") (pinfunction "A_A") (pintype "passive"))
      (node (ref "IC2-CHARGER") (pin "6") (pinfunction "VIN_6") (pintype "input"))
      (node (ref "R14") (pin "2") (pinfunction "2_2") (pintype "passive"))
      (node (ref "S4") (pin "1") (pinfunction "G_1") (pintype "passive"))
      (node (ref "USB-ON") (pin "A") (pinfunction "A_A") (pintype "passive"))
      (node (ref "USBC") (pin "A9") (pinfunction "VBUS_A9") (pintype "power_in"))
      (node (ref "USBC") (pin "B9") (pinfunction "VBUS_B9") (pintype "power_in"))
    )
    (net (code "34") (name "/VBATT_MEASURE") (class "Default")
      (node (ref "R4") (pin "2") (pinfunction "2_2") (pintype "passive"))
      (node (ref "R5") (pin "1") (pinfunction "1_1") (pintype "passive"))
      (node (ref "U1") (pin "19") (pinfunction "ADC6_19") (pintype "bidirectional"))
    )
    (net (code "35") (name "/VBOOST") (class "Default")
      (node (ref "C41") (pin "2") (pinfunction "2_2") (pintype "passive"))
      (node (ref "C6") (pin "2") (pinfunction "2_2") (pintype "passive"))
      (node (ref "D31") (pin "C") (pinfunction "C_C") (pintype "passive"))
      (node (ref "D41") (pin "C") (pinfunction "C_C") (pintype "passive"))
      (node (ref "E-FUSE-SWITCH") (pin "1") (pinfunction "P$1_1") (pintype "bidirectional"))
      (node (ref "R32") (pin "1") (pinfunction "1_1") (pintype "passive"))
      (node (ref "R35") (pin "2") (pinfunction "S_2") (pintype "passive"))
      (node (ref "VBOOST") (pin "P$1") (pinfunction "P$1_P$1") (pintype "bidirectional"))
    )
    (net (code "36") (name "/VBOOST2") (class "Default")
      (node (ref "E-FUSE-SWITCH") (pin "2") (pinfunction "P$2_2") (pintype "bidirectional"))
      (node (ref "IC4-E-FUSE") (pin "4") (pinfunction "IN_4") (pintype "input"))
      (node (ref "R41") (pin "2") (pinfunction "2_2") (pintype "passive"))
      (node (ref "R46") (pin "2") (pinfunction "2_2") (pintype "passive"))
    )
    (net (code "37") (name "/VIN5V") (class "Default")
      (node (ref "5V-SWITCH") (pin "2") (pinfunction "P$2_2") (pintype "bidirectional"))
      (node (ref "C51") (pin "2") (pinfunction "2_2") (pintype "passive"))
      (node (ref "D53") (pin "K") (pinfunction "C_K") (pintype "passive"))
      (node (ref "IC5-5V") (pin "1") (pinfunction "VIN_1") (pintype "input"))
      (node (ref "IC5-5V") (pin "3") (pinfunction "ON/~{OFF}_3") (pintype "input"))
    )
    (net (code "38") (name "/VOUT") (class "Default")
      (node (ref "5V-SWITCH") (pin "1") (pinfunction "P$1_1") (pintype "bidirectional"))
      (node (ref "C43") (pin "1") (pinfunction "1_1") (pintype "passive"))
      (node (ref "C44") (pin "2") (pinfunction "2_2") (pintype "passive"))
      (node (ref "D42") (pin "C") (pinfunction "C_C") (pintype "passive"))
      (node (ref "IC4-E-FUSE") (pin "5") (pinfunction "OUT_5") (pintype "output"))
      (node (ref "R18") (pin "2") (pinfunction "2_2") (pintype "passive"))
      (node (ref "VOUT") (pin "P$1") (pinfunction "P$1_P$1") (pintype "bidirectional"))
      (node (ref "VOUT'") (pin "P$1") (pinfunction "P$1_P$1") (pintype "bidirectional"))
    )
    (net (code "39") (name "/VOUT_MEASURE") (class "Default")
      (node (ref "R17") (pin "2") (pinfunction "2_2") (pintype "passive"))
      (node (ref "R18") (pin "1") (pinfunction "1_1") (pintype "passive"))
      (node (ref "U1") (pin "23") (pinfunction "PC0_23") (pintype "bidirectional"))
    )
    (net (code "40") (name "/VREF_2.5V") (class "Default")
      (node (ref "R27") (pin "2") (pinfunction "2_2") (pintype "passive"))
      (node (ref "U1") (pin "28") (pinfunction "PC5_28") (pintype "bidirectional"))
      (node (ref "VREF_SHUNT") (pin "1") (pinfunction "C_1") (pintype "bidirectional"))
    )
    (net (code "41") (name "/XTAL1") (class "Default")
      (node (ref "20MHZ") (pin "2") (pinfunction "2_2") (pintype "passive"))
      (node (ref "C3") (pin "2") (pinfunction "2_2") (pintype "passive"))
      (node (ref "U1") (pin "7") (pinfunction "PB6_7") (pintype "bidirectional"))
    )
    (net (code "42") (name "/XTAL2") (class "Default")
      (node (ref "20MHZ") (pin "1") (pinfunction "1_1") (pintype "passive"))
      (node (ref "C7") (pin "2") (pinfunction "2_2") (pintype "passive"))
      (node (ref "U1") (pin "8") (pinfunction "PB7_8") (pintype "bidirectional"))
    )
    (net (code "43") (name "GND") (class "Default")
      (node (ref "BUZZER") (pin "P$2") (pinfunction "P$2_P$2") (pintype "bidirectional"))
      (node (ref "C10") (pin "2") (pinfunction "2_2") (pintype "passive"))
      (node (ref "C12") (pin "2") (pinfunction "2_2") (pintype "passive"))
      (node (ref "C13") (pin "2") (pinfunction "2_2") (pintype "passive"))
      (node (ref "C16") (pin "2") (pinfunction "2_2") (pintype "passive"))
      (node (ref "C17") (pin "2") (pinfunction "2_2") (pintype "passive"))
      (node (ref "C2") (pin "1") (pinfunction "1_1") (pintype "passive"))
      (node (ref "C21") (pin "1") (pinfunction "1_1") (pintype "passive"))
      (node (ref "C3") (pin "1") (pinfunction "1_1") (pintype "passive"))
      (node (ref "C31") (pin "1") (pinfunction "1_1") (pintype "passive"))
      (node (ref "C4") (pin "2") (pinfunction "2_2") (pintype "passive"))
      (node (ref "C41") (pin "1") (pinfunction "1_1") (pintype "passive"))
      (node (ref "C42") (pin "1") (pinfunction "1_1") (pintype "passive"))
      (node (ref "C43") (pin "2") (pinfunction "2_2") (pintype "passive"))
      (node (ref "C44") (pin "1") (pinfunction "1_1") (pintype "passive"))
      (node (ref "C5") (pin "2") (pinfunction "2_2") (pintype "passive"))
      (node (ref "C51") (pin "1") (pinfunction "1_1") (pintype "passive"))
      (node (ref "C52") (pin "1") (pinfunction "1_1") (pintype "passive"))
      (node (ref "C53") (pin "1") (pinfunction "1_1") (pintype "passive"))
      (node (ref "C6") (pin "1") (pinfunction "1_1") (pintype "passive"))
      (node (ref "C7") (pin "1") (pinfunction "1_1") (pintype "passive"))
      (node (ref "C8") (pin "1") (pinfunction "1_1") (pintype "passive"))
      (node (ref "C9") (pin "2") (pinfunction "2_2") (pintype "passive"))
      (node (ref "D41") (pin "A") (pinfunction "A_A") (pintype "passive"))
      (node (ref "D42") (pin "A") (pinfunction "A_A") (pintype "passive"))
      (node (ref "DISPLAY") (pin "GND") (pinfunction "GND_GND") (pintype "bidirectional"))
      (node (ref "ESD_D1") (pin "2") (pinfunction "VN_2") (pintype "power_in"))
      (node (ref "GND") (pin "P$1") (pinfunction "P$1_P$1") (pintype "bidirectional"))
      (node (ref "GND1") (pin "P$1") (pinfunction "P$1_P$1") (pintype "bidirectional"))
      (node (ref "GND2") (pin "P$1") (pinfunction "P$1_P$1") (pintype "bidirectional"))
      (node (ref "GND3") (pin "P$1") (pinfunction "P$1_P$1") (pintype "bidirectional"))
      (node (ref "GND4") (pin "P$1") (pinfunction "P$1_P$1") (pintype "bidirectional"))
      (node (ref "IC1-BATT-PROTECT") (pin "1") (pinfunction "VM1_1") (pintype "power_in"))
      (node (ref "IC1-BATT-PROTECT") (pin "2") (pinfunction "VM2_2") (pintype "power_in"))
      (node (ref "IC1-BATT-PROTECT") (pin "3") (pinfunction "VM3_3") (pintype "power_in"))
      (node (ref "IC1-BATT-PROTECT") (pin "4") (pinfunction "VM4_4") (pintype "power_in"))
      (node (ref "IC2-CHARGER") (pin "5") (pinfunction "GND_5") (pintype "power_in"))
      (node (ref "IC3") (pin "2") (pinfunction "GND_2") (pintype "input"))
      (node (ref "IC4-E-FUSE") (pin "1") (pinfunction "GND_1") (pintype "power_in"))
      (node (ref "IC4-E-FUSE") (pin "10") (pinfunction "EPAD_10") (pintype "power_in"))
      (node (ref "IC4-E-FUSE") (pin "11") (pinfunction "EPAD_11") (pintype "power_in"))
      (node (ref "IC4-E-FUSE") (pin "12") (pinfunction "EPAD_12") (pintype "power_in"))
      (node (ref "IC4-E-FUSE") (pin "13") (pinfunction "EPAD_13") (pintype "power_in"))
      (node (ref "IC4-E-FUSE") (pin "14") (pinfunction "EPAD_14") (pintype "power_in"))
      (node (ref "IC4-E-FUSE") (pin "15") (pinfunction "EPAD_15") (pintype "power_in"))
      (node (ref "IC4-E-FUSE") (pin "16") (pinfunction "EPAD_16") (pintype "power_in"))
      (node (ref "IC4-E-FUSE") (pin "17") (pinfunction "EPAD_17") (pintype "power_in"))
      (node (ref "IC4-E-FUSE") (pin "9") (pinfunction "EPAD_9") (pintype "power_in"))
      (node (ref "IC5-5V") (pin "2") (pinfunction "GND_2") (pintype "power_in"))
      (node (ref "IC6-I-SENSE") (pin "5") (pinfunction "GND_5") (pintype "power_in"))
      (node (ref "ICSP") (pin "GND") (pinfunction "6_GND") (pintype "passive"))
      (node (ref "LOGIC-PROBE") (pin "2") (pinfunction "P$2_2") (pintype "bidirectional"))
      (node (ref "POW~12V") (pin "C") (pinfunction "C_C") (pintype "passive"))
      (node (ref "R14") (pin "1") (pinfunction "1_1") (pintype "passive"))
      (node (ref "R17") (pin "1") (pinfunction "1_1") (pintype "passive"))
      (node (ref "R2") (pin "2") (pinfunction "2_2") (pintype "passive"))
      (node (ref "R22") (pin "1") (pinfunction "1_1") (pintype "passive"))
      (node (ref "R26") (pin "1") (pinfunction "1_1") (pintype "passive"))
      (node (ref "R31") (pin "2") (pinfunction "2_2") (pintype "passive"))
      (node (ref "R37") (pin "1") (pinfunction "1_1") (pintype "passive"))
      (node (ref "R38") (pin "1") (pinfunction "1_1") (pintype "passive"))
      (node (ref "R43") (pin "1") (pinfunction "1_1") (pintype "passive"))
      (node (ref "R47") (pin "1") (pinfunction "1_1") (pintype "passive"))
      (node (ref "R5") (pin "2") (pinfunction "2_2") (pintype "passive"))
      (node (ref "R8") (pin "2") (pinfunction "2_2") (pintype "passive"))
      (node (ref "RD1") (pin "1") (pinfunction "1_1") (pintype "passive"))
      (node (ref "RD2") (pin "1") (pinfunction "1_1") (pintype "passive"))
      (node (ref "RILIM1") (pin "1") (pinfunction "1_1") (pintype "passive"))
      (node (ref "RILIM2") (pin "1") (pinfunction "1_1") (pintype "passive"))
      (node (ref "RISET") (pin "2") (pinfunction "2_2") (pintype "passive"))
      (node (ref "ROTARY-ENCODER") (pin "C") (pinfunction "C_C") (pintype "bidirectional"))
      (node (ref "S1") (pin "2") (pinfunction "2_2") (pintype "bidirectional"))
      (node (ref "S2") (pin "4") (pinfunction "GND_4") (pintype "power_in"))
      (node (ref "S3") (pin "2") (pinfunction "E_2") (pintype "passive"))
      (node (ref "S6") (pin "2") (pinfunction "S_2") (pintype "passive"))
      (node (ref "TVS_D2") (pin "A") (pinfunction "A_A") (pintype "passive"))
      (node (ref "U1") (pin "21") (pinfunction "GND_21") (pintype "power_in"))
      (node (ref "U1") (pin "3") (pinfunction "GND_3") (pintype "power_in"))
      (node (ref "U1") (pin "5") (pinfunction "GND_5") (pintype "power_in"))
      (node (ref "USBC") (pin "A12") (pinfunction "GND_A12") (pintype "bidirectional"))
      (node (ref "USBC") (pin "B12") (pinfunction "GND_B12") (pintype "bidirectional"))
      (node (ref "VIN-ON") (pin "C") (pinfunction "C_C") (pintype "passive"))
      (node (ref "VREF_SHUNT") (pin "2") (pinfunction "A_2") (pintype "bidirectional"))
      (node (ref "VREF_SHUNT") (pin "3") (pinfunction "NC/A_3") (pintype "bidirectional"))
    )
    (net (code "44") (name "Net-(CHARGING-PadA)") (class "Default")
      (node (ref "CHARGING") (pin "A") (pinfunction "A_A") (pintype "passive"))
      (node (ref "R21") (pin "1") (pinfunction "1_1") (pintype "passive"))
    )
    (net (code "45") (name "Net-(D4-A1)") (class "Default")
      (node (ref "D4") (pin "1") (pinfunction "A1_1") (pintype "bidirectional"))
      (node (ref "S1") (pin "C") (pinfunction "C_C") (pintype "bidirectional"))
    )
    (net (code "46") (name "Net-(FAULT-PadA)") (class "Default")
      (node (ref "FAULT") (pin "A") (pinfunction "A_A") (pintype "passive"))
      (node (ref "R48") (pin "1") (pinfunction "1_1") (pintype "passive"))
    )
    (net (code "47") (name "Net-(FLASHLIGHT-P$1)") (class "Default")
      (node (ref "FLASHLIGHT") (pin "+VE") (pinfunction "P$1_+VE") (pintype "bidirectional"))
      (node (ref "R7") (pin "2") (pinfunction "2_2") (pintype "passive"))
    )
    (net (code "48") (name "Net-(FLASHLIGHT-P$2)") (class "Default")
      (node (ref "FLASHLIGHT") (pin "-VE") (pinfunction "P$2_-VE") (pintype "bidirectional"))
      (node (ref "S6") (pin "3") (pinfunction "D_3") (pintype "passive"))
    )
    (net (code "49") (name "Net-(I-SENSE-HEADER-P$1)") (class "Default")
      (node (ref "I-SENSE-HEADER") (pin "1") (pinfunction "P$1_1") (pintype "bidirectional"))
      (node (ref "IC6-I-SENSE") (pin "1") (pinfunction "IN+_1") (pintype "input"))
      (node (ref "IC6-I-SENSE") (pin "2") (pinfunction "IN+_2") (pintype "input"))
    )
    (net (code "50") (name "Net-(I-SENSE-HEADER-P$2)") (class "Default")
      (node (ref "I-SENSE-HEADER") (pin "2") (pinfunction "P$2_2") (pintype "bidirectional"))
      (node (ref "IC6-I-SENSE") (pin "3") (pinfunction "IN-_3") (pintype "output"))
      (node (ref "IC6-I-SENSE") (pin "4") (pinfunction "IN-_4") (pintype "output"))
    )
    (net (code "51") (name "Net-(IC1-BATT-PROTECT-VDD)") (class "Default")
      (node (ref "C1") (pin "1") (pinfunction "1_1") (pintype "passive"))
      (node (ref "IC1-BATT-PROTECT") (pin "6") (pinfunction "VDD_6") (pintype "power_in"))
      (node (ref "R1") (pin "1") (pinfunction "1_1") (pintype "passive"))
    )
    (net (code "52") (name "Net-(IC2-CHARGER-ISET)") (class "Default")
      (node (ref "IC2-CHARGER") (pin "4") (pinfunction "ISET_4") (pintype "input"))
      (node (ref "RISET") (pin "1") (pinfunction "1_1") (pintype "passive"))
    )
    (net (code "53") (name "Net-(IC2-CHARGER-~{CHG})") (class "Default")
      (node (ref "CHARGING") (pin "C") (pinfunction "C_C") (pintype "passive"))
      (node (ref "IC2-CHARGER") (pin "3") (pinfunction "~{CHG}_3") (pintype "output"))
    )
    (net (code "54") (name "Net-(IC4-E-FUSE-DVDT)") (class "Default")
      (node (ref "C42") (pin "2") (pinfunction "2_2") (pintype "passive"))
      (node (ref "IC4-E-FUSE") (pin "2") (pinfunction "DVDT_2") (pintype "input"))
    )
    (net (code "55") (name "Net-(IC4-E-FUSE-EN{slash}UVLO)") (class "Default")
      (node (ref "IC4-E-FUSE") (pin "3") (pinfunction "EN/UVLO_3") (pintype "input"))
      (node (ref "R41") (pin "1") (pinfunction "1_1") (pintype "passive"))
      (node (ref "R42") (pin "2") (pinfunction "2_2") (pintype "passive"))
    )
    (net (code "56") (name "Net-(IC4-E-FUSE-ILM)") (class "Default")
      (node (ref "IC4-E-FUSE") (pin "7") (pinfunction "ILM_7") (pintype "input"))
      (node (ref "ILIMIT") (pin "2") (pinfunction "P$2_2") (pintype "bidirectional"))
    )
    (net (code "57") (name "Net-(IC4-E-FUSE-OVLO)") (class "Default")
      (node (ref "IC4-E-FUSE") (pin "8") (pinfunction "OVLO_8") (pintype "output"))
      (node (ref "R42") (pin "1") (pinfunction "1_1") (pintype "passive"))
      (node (ref "R43") (pin "2") (pinfunction "2_2") (pintype "passive"))
    )
    (net (code "58") (name "Net-(IC4-E-FUSE-~{FLT})") (class "Default")
      (node (ref "FAULT") (pin "C") (pinfunction "C_C") (pintype "passive"))
      (node (ref "IC4-E-FUSE") (pin "6") (pinfunction "~{FLT}_6") (pintype "tri_state"))
    )
    (net (code "59") (name "Net-(IC5-5V-BYPASS)") (class "Default")
      (node (ref "C53") (pin "2") (pinfunction "2_2") (pintype "passive"))
      (node (ref "IC5-5V") (pin "4") (pinfunction "BYPASS_4") (pintype "input"))
    )
    (net (code "60") (name "Net-(ILIMIT-P$1)") (class "Default")
      (node (ref "ILIMIT") (pin "1") (pinfunction "P$1_1") (pintype "bidirectional"))
      (node (ref "RILIM1") (pin "2") (pinfunction "2_2") (pintype "passive"))
    )
    (net (code "61") (name "Net-(ILIMIT-P$3)") (class "Default")
      (node (ref "ILIMIT") (pin "3") (pinfunction "P$3_3") (pintype "bidirectional"))
      (node (ref "RILIM2") (pin "2") (pinfunction "2_2") (pintype "passive"))
    )
    (net (code "62") (name "Net-(POW~12V-PadA)") (class "Default")
      (node (ref "POW~12V") (pin "A") (pinfunction "A_A") (pintype "passive"))
      (node (ref "R46") (pin "1") (pinfunction "1_1") (pintype "passive"))
      (node (ref "R47") (pin "2") (pinfunction "2_2") (pintype "passive"))
    )
    (net (code "63") (name "Net-(R3-Pad1)") (class "Default")
      (node (ref "R3") (pin "1") (pinfunction "1_1") (pintype "passive"))
      (node (ref "VIN-ON") (pin "A") (pinfunction "A_A") (pintype "passive"))
    )
    (net (code "64") (name "Net-(R16-Pad1)") (class "Default")
      (node (ref "R16") (pin "1") (pinfunction "1_1") (pintype "passive"))
      (node (ref "R30") (pin "1") (pinfunction "1_1") (pintype "passive"))
      (node (ref "ROTARY-ENCODER") (pin "A") (pinfunction "A_A") (pintype "bidirectional"))
    )
    (net (code "65") (name "Net-(R19-Pad1)") (class "Default")
      (node (ref "R19") (pin "1") (pinfunction "1_1") (pintype "passive"))
      (node (ref "R29") (pin "1") (pinfunction "1_1") (pintype "passive"))
      (node (ref "ROTARY-ENCODER") (pin "B") (pinfunction "B_B") (pintype "bidirectional"))
    )
    (net (code "66") (name "Net-(R22-Pad2)") (class "Default")
      (node (ref "R22") (pin "2") (pinfunction "2_2") (pintype "passive"))
      (node (ref "USB-ON") (pin "C") (pinfunction "C_C") (pintype "passive"))
    )
    (net (code "67") (name "Net-(R32-Pad2)") (class "Default")
      (node (ref "R32") (pin "2") (pinfunction "2_2") (pintype "passive"))
      (node (ref "VBOOST-SEL") (pin "1") (pinfunction "1_1") (pintype "bidirectional"))
    )
    (net (code "68") (name "Net-(R34-Pad2)") (class "Default")
      (node (ref "R34") (pin "2") (pinfunction "2_2") (pintype "passive"))
      (node (ref "VBOOST-SEL") (pin "2") (pinfunction "2_2") (pintype "bidirectional"))
    )
    (net (code "69") (name "Net-(R35-CCW)") (class "Default")
      (node (ref "R34") (pin "1") (pinfunction "1_1") (pintype "passive"))
      (node (ref "R35") (pin "3") (pinfunction "CCW_3") (pintype "passive"))
    )
    (net (code "70") (name "Net-(S2-RT)") (class "Default")
      (node (ref "R2") (pin "1") (pinfunction "1_1") (pintype "passive"))
      (node (ref "S2") (pin "6") (pinfunction "RT_6") (pintype "output"))
    )
    (net (code "71") (name "Net-(S3-B)") (class "Default")
      (node (ref "R36") (pin "1") (pinfunction "1_1") (pintype "passive"))
      (node (ref "S3") (pin "1") (pinfunction "B_1") (pintype "passive"))
    )
    (net (code "72") (name "Net-(USBC-CC1)") (class "Default")
      (node (ref "RD1") (pin "2") (pinfunction "2_2") (pintype "passive"))
      (node (ref "USBC") (pin "A5") (pinfunction "CC1_A5") (pintype "bidirectional"))
    )
    (net (code "73") (name "Net-(USBC-CC2)") (class "Default")
      (node (ref "RD2") (pin "2") (pinfunction "2_2") (pintype "passive"))
      (node (ref "USBC") (pin "B5") (pinfunction "CC2_B5") (pintype "bidirectional"))
    )
    (net (code "74") (name "VIN") (class "Default")
      (node (ref "C31") (pin "2") (pinfunction "2_2") (pintype "passive"))
      (node (ref "D5") (pin "C") (pinfunction "C_C") (pintype "passive"))
      (node (ref "IC3") (pin "4") (pinfunction "EN_4") (pintype "output"))
      (node (ref "IC3") (pin "5") (pinfunction "VIN_5") (pintype "input"))
      (node (ref "L31") (pin "P$1") (pinfunction "P$1_P$1") (pintype "bidirectional"))
      (node (ref "R3") (pin "2") (pinfunction "2_2") (pintype "passive"))
      (node (ref "R4") (pin "1") (pinfunction "1_1") (pintype "passive"))
      (node (ref "R48") (pin "2") (pinfunction "2_2") (pintype "passive"))
      (node (ref "S4") (pin "2") (pinfunction "S_2") (pintype "passive"))
      (node (ref "VIN") (pin "P$1") (pinfunction "P$1_P$1") (pintype "bidirectional"))
      (node (ref "VIN'") (pin "P$1") (pinfunction "P$1_P$1") (pintype "bidirectional"))
    )
    (net (code "75") (name "unconnected-(IC2-CHARGER-TS-Pad1)") (class "Default")
      (node (ref "IC2-CHARGER") (pin "1") (pinfunction "TS_1") (pintype "input"))
    )
    (net (code "76") (name "unconnected-(IC3-NC-Pad6)") (class "Default")
      (node (ref "IC3") (pin "6") (pinfunction "NC_6") (pintype "no_connect"))
    )
    (net (code "77") (name "unconnected-(IC6-I-SENSE-NC-Pad6)") (class "Default")
      (node (ref "IC6-I-SENSE") (pin "6") (pinfunction "NC_6") (pintype "output"))
    )
    (net (code "78") (name "unconnected-(R35-CW-Pad1)") (class "Default")
      (node (ref "R35") (pin "1") (pinfunction "CW_1") (pintype "passive"))
    )
    (net (code "79") (name "unconnected-(USBC-PadSH1)") (class "Default")
      (node (ref "USBC") (pin "SH1") (pinfunction "SH1_SH1") (pintype "bidirectional"))
    )
    (net (code "80") (name "unconnected-(USBC-PadSH2)") (class "Default")
      (node (ref "USBC") (pin "SH2") (pinfunction "SH2_SH2") (pintype "bidirectional"))
    )
    (net (code "81") (name "unconnected-(USBC-PadSH3)") (class "Default")
      (node (ref "USBC") (pin "SH3") (pinfunction "SH3_SH3") (pintype "bidirectional"))
    )
    (net (code "82") (name "unconnected-(USBC-PadSH4)") (class "Default")
      (node (ref "USBC") (pin "SH4") (pinfunction "SH4_SH4") (pintype "bidirectional"))
    )
  )
)
